# Flash.net
KiCad netlist of a schematic drawn in Altium Designer
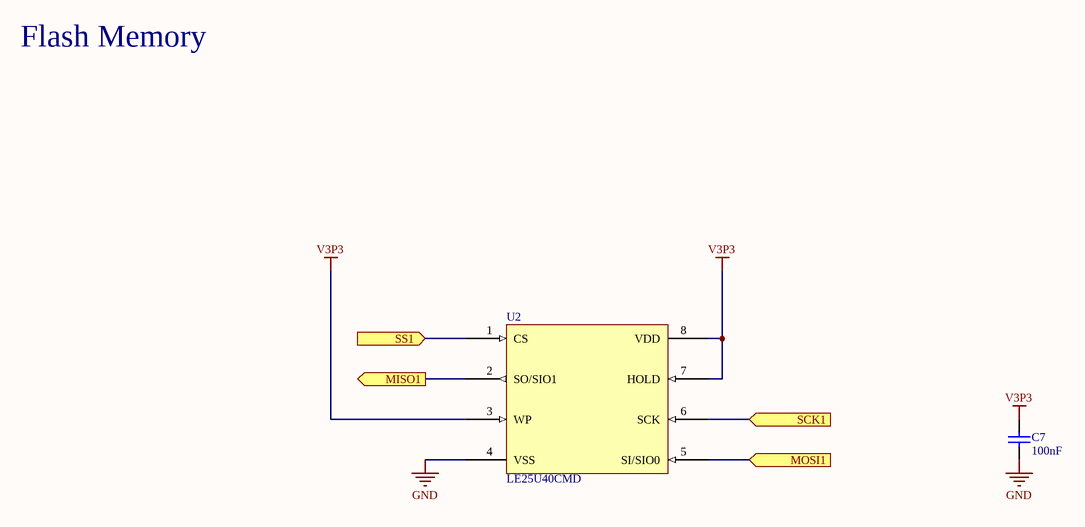
[diagram p0: Flash.SchDoc]

(export (version "E")
  (design (tool "Eeschema 10.0.6"))
  (components
    (comp (ref "C7")
      (value "100nF")
      (footprint "own_0603")
      (description "Capacitor")
      (libsource (lib "Miscellaneous Devices") (part "Cap"))
    )
    (comp (ref "U2")
      (value "LE25U40CMD")
      (footprint "LE25U40CMDTWG")
      (description "Flash memory")
      (libsource (lib "Schlib") (part "LE25U40CMD"))
    )
  )
  (nets
    (net (code "1") (name "/MISO1") (class "Default")
      (node (ref "U2") (pin "2") (pinfunction "SO/SIO1_2") (pintype "output"))
    )
    (net (code "2") (name "/MOSI1") (class "Default")
      (node (ref "U2") (pin "5") (pinfunction "SI/SIO0_5") (pintype "input"))
    )
    (net (code "3") (name "/SCK1") (class "Default")
      (node (ref "U2") (pin "6") (pinfunction "SCK_6") (pintype "input"))
    )
    (net (code "4") (name "/SS1") (class "Default")
      (node (ref "U2") (pin "1") (pinfunction "CS_1") (pintype "input"))
    )
    (net (code "5") (name "GND") (class "Default")
      (node (ref "C7") (pin "1") (pinfunction "1_1") (pintype "passive"))
      (node (ref "U2") (pin "4") (pinfunction "VSS_4") (pintype "power_in"))
    )
    (net (code "6") (name "V3P3") (class "Default")
      (node (ref "C7") (pin "2") (pinfunction "2_2") (pintype "passive"))
      (node (ref "U2") (pin "3") (pinfunction "WP_3") (pintype "input"))
      (node (ref "U2") (pin "7") (pinfunction "HOLD_7") (pintype "input"))
      (node (ref "U2") (pin "8") (pinfunction "VDD_8") (pintype "power_in"))
    )
  )
)
